# BpodFSM_r2_3.net
KiCad netlist of a schematic drawn in EAGLE
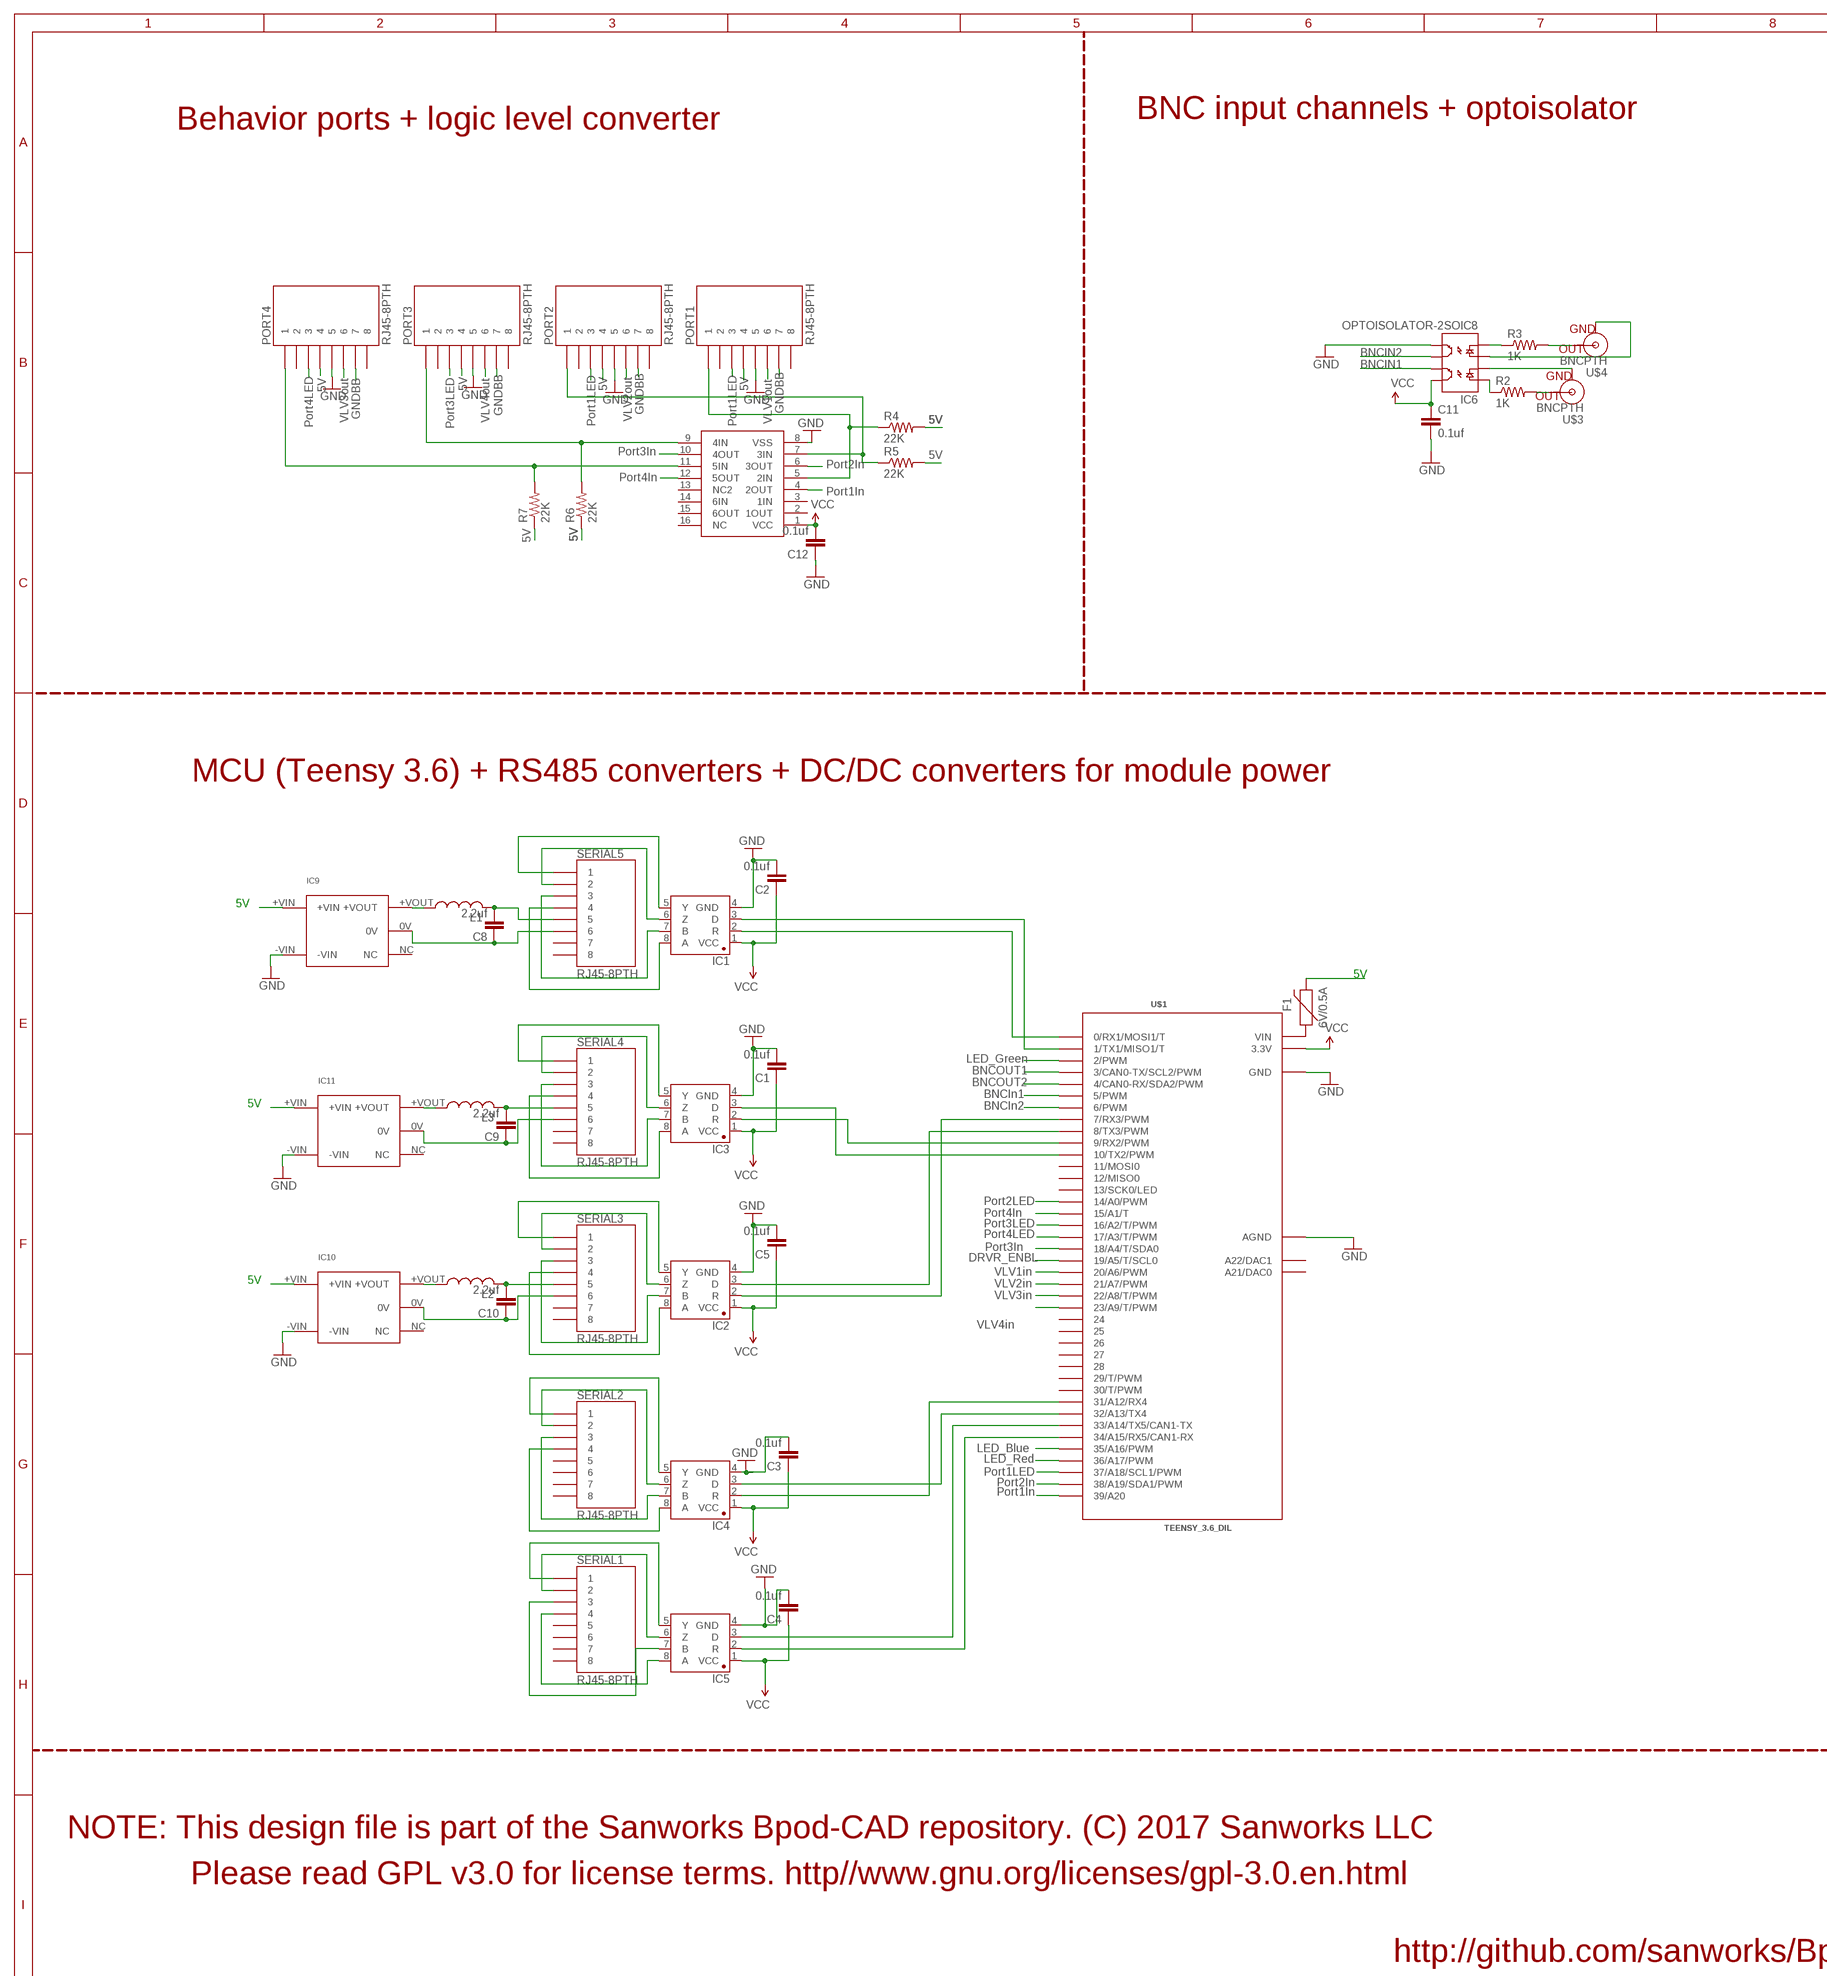
[diagram p0: schematic, sheet 1, part 1 of 2]
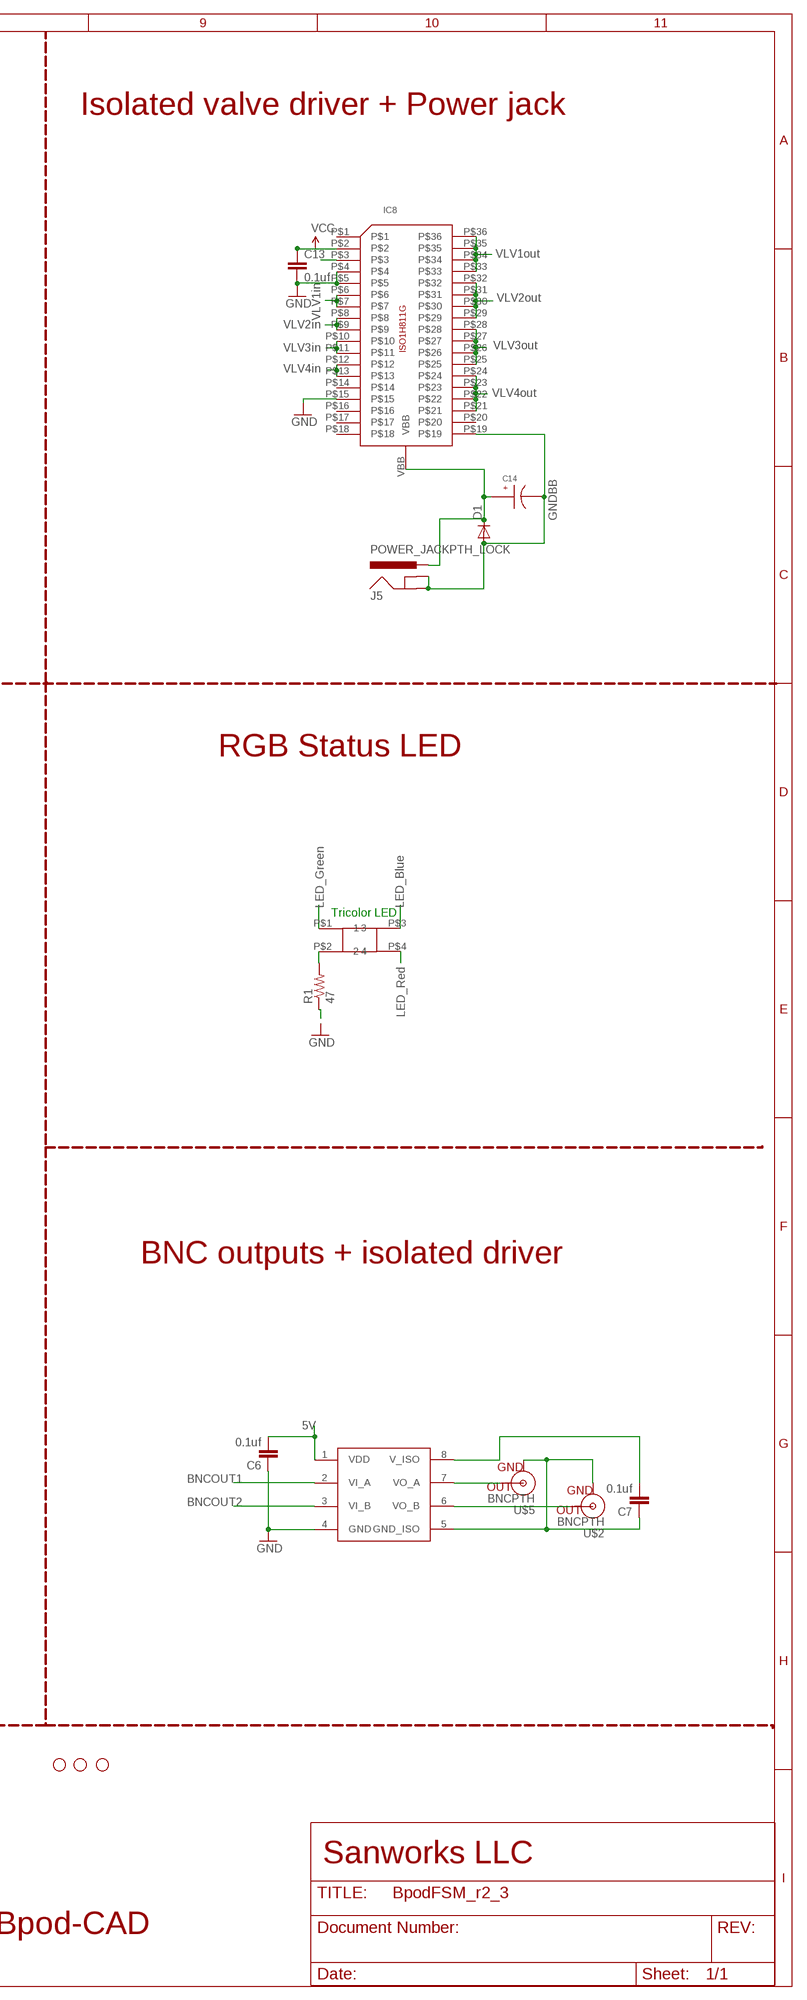
[diagram p1: schematic, sheet 1, part 2 of 2]

(export (version "E")
  (design (tool "Eeschema 10.0.6"))
  (components
    (comp (ref "C1")
      (value "0.1uf")
      (footprint "eagle-import:1206")
      (libsource (lib "eagle-import") (part "CAP1206"))
    )
    (comp (ref "C2")
      (value "0.1uf")
      (footprint "eagle-import:1206")
      (libsource (lib "eagle-import") (part "CAP1206"))
    )
    (comp (ref "C3")
      (value "0.1uf")
      (footprint "eagle-import:1206")
      (libsource (lib "eagle-import") (part "CAP1206"))
    )
    (comp (ref "C4")
      (value "0.1uf")
      (footprint "eagle-import:1206")
      (libsource (lib "eagle-import") (part "CAP1206"))
    )
    (comp (ref "C5")
      (value "0.1uf")
      (footprint "eagle-import:1206")
      (libsource (lib "eagle-import") (part "CAP1206"))
    )
    (comp (ref "C6")
      (value "0.1uf")
      (footprint "eagle-import:1206")
      (libsource (lib "eagle-import") (part "CAP1206"))
    )
    (comp (ref "C7")
      (value "0.1uf")
      (footprint "eagle-import:1206")
      (libsource (lib "eagle-import") (part "CAP1206"))
    )
    (comp (ref "C8")
      (value "2.2uf")
      (footprint "eagle-import:1206")
      (libsource (lib "eagle-import") (part "CAP1206"))
    )
    (comp (ref "C9")
      (value "2.2uf")
      (footprint "eagle-import:1206")
      (libsource (lib "eagle-import") (part "CAP1206"))
    )
    (comp (ref "C10")
      (value "2.2uf")
      (footprint "eagle-import:1206")
      (libsource (lib "eagle-import") (part "CAP1206"))
    )
    (comp (ref "C11")
      (value "0.1uf")
      (footprint "eagle-import:1206")
      (libsource (lib "eagle-import") (part "CAP1206"))
    )
    (comp (ref "C12")
      (value "0.1uf")
      (footprint "eagle-import:1206")
      (libsource (lib "eagle-import") (part "CAP1206"))
    )
    (comp (ref "C13")
      (value "0.1uf")
      (footprint "eagle-import:1206")
      (libsource (lib "eagle-import") (part "CAP1206"))
    )
    (comp (ref "C14")
      (value "EEE-FK1H100UR")
      (footprint "eagle-import:EEE-FK1H100UR")
      (libsource (lib "eagle-import") (part "EEE-FK1H100UR"))
    )
    (comp (ref "D1")
      (value "DIODE-DO214AA")
      (footprint "eagle-import:DO214AA")
      (libsource (lib "eagle-import") (part "DIODE-DO214AA"))
    )
    (comp (ref "F1")
      (value "6V/0.5A")
      (footprint "eagle-import:1206")
      (libsource (lib "eagle-import") (part "PPTC_HALF-AMP"))
    )
    (comp (ref "IC1")
      (value "SN65HVD31DR")
      (footprint "eagle-import:SO08")
      (libsource (lib "eagle-import") (part "SN65HVD31DR"))
    )
    (comp (ref "IC2")
      (value "SN65HVD31DR")
      (footprint "eagle-import:SO08")
      (libsource (lib "eagle-import") (part "SN65HVD31DR"))
    )
    (comp (ref "IC3")
      (value "SN65HVD31DR")
      (footprint "eagle-import:SO08")
      (libsource (lib "eagle-import") (part "SN65HVD31DR"))
    )
    (comp (ref "IC4")
      (value "SN65HVD31DR")
      (footprint "eagle-import:SO08")
      (libsource (lib "eagle-import") (part "SN65HVD31DR"))
    )
    (comp (ref "IC5")
      (value "SN65HVD31DR")
      (footprint "eagle-import:SO08")
      (libsource (lib "eagle-import") (part "SN65HVD31DR"))
    )
    (comp (ref "IC6")
      (value "OPTOISOLATOR-2SOIC8")
      (footprint "eagle-import:SO08-2")
      (libsource (lib "eagle-import") (part "OPTOISOLATOR-2SOIC8"))
    )
    (comp (ref "IC7")
      (value "ADUM5240")
      (footprint "eagle-import:SO08")
      (libsource (lib "eagle-import") (part "ADUM5240"))
    )
    (comp (ref "IC8")
      (value "ISO1H811G")
      (footprint "eagle-import:ISO1H811G")
      (libsource (lib "eagle-import") (part "ISO1H811G"))
    )
    (comp (ref "IC9")
      (value "MTU1D0505MC")
      (footprint "eagle-import:MTU1D0505MC")
      (libsource (lib "eagle-import") (part "MTU1D0505MC"))
    )
    (comp (ref "IC10")
      (value "MTU1D0505MC")
      (footprint "eagle-import:MTU1D0505MC")
      (libsource (lib "eagle-import") (part "MTU1D0505MC"))
    )
    (comp (ref "IC11")
      (value "MTU1D0505MC")
      (footprint "eagle-import:MTU1D0505MC")
      (libsource (lib "eagle-import") (part "MTU1D0505MC"))
    )
    (comp (ref "IC12")
      (value "CD4050")
      (footprint "eagle-import:SO16")
      (libsource (lib "eagle-import") (part "CD4050"))
    )
    (comp (ref "J5")
      (value "POWER_JACKPTH_LOCK")
      (footprint "eagle-import:POWER_JACK_PTH_LOCK")
      (libsource (lib "eagle-import") (part "POWER_JACKPTH_LOCK"))
    )
    (comp (ref "JP3")
      (value "STAND-OFF")
      (footprint "eagle-import:STAND-OFF")
      (libsource (lib "eagle-import") (part "STAND-OFF"))
    )
    (comp (ref "JP4")
      (value "STAND-OFF")
      (footprint "eagle-import:STAND-OFF")
      (libsource (lib "eagle-import") (part "STAND-OFF"))
    )
    (comp (ref "JP5")
      (value "STAND-OFF")
      (footprint "eagle-import:STAND-OFF")
      (libsource (lib "eagle-import") (part "STAND-OFF"))
    )
    (comp (ref "L1")
      (value "L-USL3225M")
      (footprint "eagle-import:L3225M")
      (libsource (lib "eagle-import") (part "L-USL3225M"))
    )
    (comp (ref "L2")
      (value "L-USL3225M")
      (footprint "eagle-import:L3225M")
      (libsource (lib "eagle-import") (part "L-USL3225M"))
    )
    (comp (ref "L3")
      (value "L-USL3225M")
      (footprint "eagle-import:L3225M")
      (libsource (lib "eagle-import") (part "L-USL3225M"))
    )
    (comp (ref "PORT1")
      (value "RJ45-8PTH")
      (footprint "eagle-import:RJ45-8")
      (libsource (lib "eagle-import") (part "RJ45-8PTH"))
    )
    (comp (ref "PORT2")
      (value "RJ45-8PTH")
      (footprint "eagle-import:RJ45-8")
      (libsource (lib "eagle-import") (part "RJ45-8PTH"))
    )
    (comp (ref "PORT3")
      (value "RJ45-8PTH")
      (footprint "eagle-import:RJ45-8")
      (libsource (lib "eagle-import") (part "RJ45-8PTH"))
    )
    (comp (ref "PORT4")
      (value "RJ45-8PTH")
      (footprint "eagle-import:RJ45-8")
      (libsource (lib "eagle-import") (part "RJ45-8PTH"))
    )
    (comp (ref "R1")
      (value "47")
      (footprint "eagle-import:1206")
      (libsource (lib "eagle-import") (part "RESISTOR1206"))
    )
    (comp (ref "R2")
      (value "1K")
      (footprint "eagle-import:1206")
      (libsource (lib "eagle-import") (part "SparkFun-Resistors_RESISTOR1206"))
    )
    (comp (ref "R3")
      (value "1K")
      (footprint "eagle-import:1206")
      (libsource (lib "eagle-import") (part "SparkFun-Resistors_RESISTOR1206"))
    )
    (comp (ref "R4")
      (value "22K")
      (footprint "eagle-import:1206")
      (libsource (lib "eagle-import") (part "SparkFun-Resistors_RESISTOR1206"))
    )
    (comp (ref "R5")
      (value "22K")
      (footprint "eagle-import:1206")
      (libsource (lib "eagle-import") (part "SparkFun-Resistors_RESISTOR1206"))
    )
    (comp (ref "R6")
      (value "22K")
      (footprint "eagle-import:1206")
      (libsource (lib "eagle-import") (part "SparkFun-Resistors_RESISTOR1206"))
    )
    (comp (ref "R7")
      (value "22K")
      (footprint "eagle-import:1206")
      (libsource (lib "eagle-import") (part "SparkFun-Resistors_RESISTOR1206"))
    )
    (comp (ref "SERIAL1")
      (value "RJ45-8PTH")
      (footprint "eagle-import:RJ45-8")
      (libsource (lib "eagle-import") (part "RJ45-8PTH"))
    )
    (comp (ref "SERIAL2")
      (value "RJ45-8PTH")
      (footprint "eagle-import:RJ45-8")
      (libsource (lib "eagle-import") (part "RJ45-8PTH"))
    )
    (comp (ref "SERIAL3")
      (value "RJ45-8PTH")
      (footprint "eagle-import:RJ45-8")
      (libsource (lib "eagle-import") (part "RJ45-8PTH"))
    )
    (comp (ref "SERIAL4")
      (value "RJ45-8PTH")
      (footprint "eagle-import:RJ45-8")
      (libsource (lib "eagle-import") (part "RJ45-8PTH"))
    )
    (comp (ref "SERIAL5")
      (value "RJ45-8PTH")
      (footprint "eagle-import:RJ45-8")
      (libsource (lib "eagle-import") (part "RJ45-8PTH"))
    )
    (comp (ref "U$1")
      (value "TEENSY_3.6_DIL")
      (footprint "eagle-import:TEENSY_3.6_DIL")
      (libsource (lib "eagle-import") (part "TEENSY_3.6_DIL"))
    )
    (comp (ref "U$2")
      (value "BNCPTH")
      (footprint "eagle-import:BNC")
      (libsource (lib "eagle-import") (part "BNCPTH"))
    )
    (comp (ref "U$3")
      (value "BNCPTH")
      (footprint "eagle-import:BNC")
      (libsource (lib "eagle-import") (part "BNCPTH"))
    )
    (comp (ref "U$4")
      (value "BNCPTH")
      (footprint "eagle-import:BNC")
      (libsource (lib "eagle-import") (part "BNCPTH"))
    )
    (comp (ref "U$5")
      (value "BNCPTH")
      (footprint "eagle-import:BNC")
      (libsource (lib "eagle-import") (part "BNCPTH"))
    )
    (comp (ref "U$8")
      (value "SQUARE_TRICOLOR_LED")
      (footprint "eagle-import:SQUARE_TRICOLOR_LED")
      (libsource (lib "eagle-import") (part "SQUARE_TRICOLOR_LED"))
    )
  )
  (nets
    (net (code "1") (name "/5V") (class "Default")
      (node (ref "C6") (pin "2") (pinfunction "2_2") (pintype "passive"))
      (node (ref "F1") (pin "2") (pinfunction "2_2") (pintype "bidirectional"))
      (node (ref "IC10") (pin "+VIN") (pinfunction "+VIN_+VIN") (pintype "bidirectional"))
      (node (ref "IC11") (pin "+VIN") (pinfunction "+VIN_+VIN") (pintype "bidirectional"))
      (node (ref "IC7") (pin "1") (pinfunction "VDD_1") (pintype "bidirectional"))
      (node (ref "IC9") (pin "+VIN") (pinfunction "+VIN_+VIN") (pintype "bidirectional"))
      (node (ref "PORT1") (pin "4") (pinfunction "4_4") (pintype "bidirectional"))
      (node (ref "PORT2") (pin "4") (pinfunction "4_4") (pintype "bidirectional"))
      (node (ref "PORT3") (pin "4") (pinfunction "4_4") (pintype "bidirectional"))
      (node (ref "PORT4") (pin "4") (pinfunction "4_4") (pintype "bidirectional"))
      (node (ref "R4") (pin "2") (pinfunction "2_2") (pintype "passive"))
      (node (ref "R5") (pin "2") (pinfunction "2_2") (pintype "passive"))
      (node (ref "R6") (pin "1") (pinfunction "1_1") (pintype "passive"))
      (node (ref "R7") (pin "1") (pinfunction "1_1") (pintype "passive"))
    )
    (net (code "2") (name "/BNCIN1") (class "Default")
      (node (ref "IC6") (pin "7") (pinfunction "EM1_7") (pintype "bidirectional"))
      (node (ref "U$1") (pin "6") (pinfunction "6/PWM_6") (pintype "bidirectional"))
    )
    (net (code "3") (name "/BNCIN2") (class "Default")
      (node (ref "IC6") (pin "6") (pinfunction "CL2_6") (pintype "bidirectional"))
      (node (ref "U$1") (pin "5") (pinfunction "5/PWM_5") (pintype "bidirectional"))
    )
    (net (code "4") (name "/BNCOUT1") (class "Default")
      (node (ref "IC7") (pin "3") (pinfunction "VI_B_3") (pintype "bidirectional"))
      (node (ref "U$1") (pin "4") (pinfunction "4/CAN0-RX/SDA2/PWM_4") (pintype "bidirectional"))
    )
    (net (code "5") (name "/BNCOUT2") (class "Default")
      (node (ref "IC7") (pin "2") (pinfunction "VI_A_2") (pintype "bidirectional"))
      (node (ref "U$1") (pin "3") (pinfunction "3/CAN0-TX/SCL2/PWM_3") (pintype "bidirectional"))
    )
    (net (code "6") (name "/DRVR_ENBL") (class "Default")
      (node (ref "IC8") (pin "P$3") (pinfunction "P$3_P$3") (pintype "bidirectional"))
      (node (ref "U$1") (pin "19/A5") (pinfunction "19/A5/T/SCL0_19/A5") (pintype "bidirectional"))
    )
    (net (code "7") (name "/GNDBB") (class "Default")
      (node (ref "C14") (pin "CATHODE") (pinfunction "CATHODE_CATHODE") (pintype "bidirectional"))
      (node (ref "D1") (pin "A") (pinfunction "A_A") (pintype "passive"))
      (node (ref "IC8") (pin "P$19") (pinfunction "P$19_P$19") (pintype "bidirectional"))
      (node (ref "J5") (pin "GND") (pinfunction "GND_GND") (pintype "bidirectional"))
      (node (ref "J5") (pin "GNDBREAK") (pinfunction "GNDBREAK_GNDBREAK") (pintype "bidirectional"))
      (node (ref "PORT1") (pin "7") (pinfunction "7_7") (pintype "bidirectional"))
      (node (ref "PORT2") (pin "7") (pinfunction "7_7") (pintype "bidirectional"))
      (node (ref "PORT3") (pin "7") (pinfunction "7_7") (pintype "bidirectional"))
      (node (ref "PORT4") (pin "7") (pinfunction "7_7") (pintype "bidirectional"))
    )
    (net (code "8") (name "/LED_BLUE") (class "Default")
      (node (ref "U$1") (pin "35/A16") (pinfunction "35/A16/PWM_35/A16") (pintype "bidirectional"))
      (node (ref "U$8") (pin "P$3") (pinfunction "3_P$3") (pintype "bidirectional"))
    )
    (net (code "9") (name "/LED_GREEN") (class "Default")
      (node (ref "U$1") (pin "2") (pinfunction "2/PWM_2") (pintype "bidirectional"))
      (node (ref "U$8") (pin "P$1") (pinfunction "1_P$1") (pintype "bidirectional"))
    )
    (net (code "10") (name "/LED_RED") (class "Default")
      (node (ref "U$1") (pin "36/A17") (pinfunction "36/A17/PWM_36/A17") (pintype "bidirectional"))
      (node (ref "U$8") (pin "P$4") (pinfunction "4_P$4") (pintype "bidirectional"))
    )
    (net (code "11") (name "/PORT1IN") (class "Default")
      (node (ref "IC12") (pin "4") (pinfunction "2OUT_4") (pintype "bidirectional"))
      (node (ref "U$1") (pin "39/A20") (pinfunction "39/A20_39/A20") (pintype "bidirectional"))
    )
    (net (code "12") (name "/PORT1LED") (class "Default")
      (node (ref "PORT1") (pin "3") (pinfunction "3_3") (pintype "bidirectional"))
      (node (ref "U$1") (pin "37/A18") (pinfunction "37/A18/SCL1/PWM_37/A18") (pintype "bidirectional"))
    )
    (net (code "13") (name "/PORT2IN") (class "Default")
      (node (ref "IC12") (pin "6") (pinfunction "3OUT_6") (pintype "bidirectional"))
      (node (ref "U$1") (pin "38/A19") (pinfunction "38/A19/SDA1/PWM_38/A19") (pintype "bidirectional"))
    )
    (net (code "14") (name "/PORT2LED") (class "Default")
      (node (ref "PORT2") (pin "3") (pinfunction "3_3") (pintype "bidirectional"))
      (node (ref "U$1") (pin "14/A0") (pinfunction "14/A0/PWM_14/A0") (pintype "bidirectional"))
    )
    (net (code "15") (name "/PORT3IN") (class "Default")
      (node (ref "IC12") (pin "10") (pinfunction "4OUT_10") (pintype "bidirectional"))
      (node (ref "U$1") (pin "18/A4") (pinfunction "18/A4/T/SDA0_18/A4") (pintype "bidirectional"))
    )
    (net (code "16") (name "/PORT3LED") (class "Default")
      (node (ref "PORT3") (pin "3") (pinfunction "3_3") (pintype "bidirectional"))
      (node (ref "U$1") (pin "16/A2") (pinfunction "16/A2/T/PWM_16/A2") (pintype "bidirectional"))
    )
    (net (code "17") (name "/PORT4IN") (class "Default")
      (node (ref "IC12") (pin "12") (pinfunction "5OUT_12") (pintype "bidirectional"))
      (node (ref "U$1") (pin "15/A1") (pinfunction "15/A1/T_15/A1") (pintype "bidirectional"))
    )
    (net (code "18") (name "/PORT4LED") (class "Default")
      (node (ref "PORT4") (pin "3") (pinfunction "3_3") (pintype "bidirectional"))
      (node (ref "U$1") (pin "17/A3") (pinfunction "17/A3/T/PWM_17/A3") (pintype "bidirectional"))
    )
    (net (code "19") (name "/VLV1IN") (class "Default")
      (node (ref "IC8") (pin "P$6") (pinfunction "P$6_P$6") (pintype "bidirectional"))
      (node (ref "IC8") (pin "P$7") (pinfunction "P$7_P$7") (pintype "bidirectional"))
      (node (ref "U$1") (pin "23/A9") (pinfunction "23/A9/T/PWM_23/A9") (pintype "bidirectional"))
    )
    (net (code "20") (name "/VLV1OUT") (class "Default")
      (node (ref "IC8") (pin "P$33") (pinfunction "P$33_P$33") (pintype "bidirectional"))
      (node (ref "IC8") (pin "P$34") (pinfunction "P$34_P$34") (pintype "bidirectional"))
      (node (ref "IC8") (pin "P$35") (pinfunction "P$35_P$35") (pintype "bidirectional"))
      (node (ref "IC8") (pin "P$36") (pinfunction "P$36_P$36") (pintype "bidirectional"))
      (node (ref "PORT1") (pin "6") (pinfunction "6_6") (pintype "bidirectional"))
    )
    (net (code "21") (name "/VLV2IN") (class "Default")
      (node (ref "IC8") (pin "P$8") (pinfunction "P$8_P$8") (pintype "bidirectional"))
      (node (ref "IC8") (pin "P$9") (pinfunction "P$9_P$9") (pintype "bidirectional"))
      (node (ref "U$1") (pin "22/A8") (pinfunction "22/A8/T/PWM_22/A8") (pintype "bidirectional"))
    )
    (net (code "22") (name "/VLV2OUT") (class "Default")
      (node (ref "IC8") (pin "P$29") (pinfunction "P$29_P$29") (pintype "bidirectional"))
      (node (ref "IC8") (pin "P$30") (pinfunction "P$30_P$30") (pintype "bidirectional"))
      (node (ref "IC8") (pin "P$31") (pinfunction "P$31_P$31") (pintype "bidirectional"))
      (node (ref "IC8") (pin "P$32") (pinfunction "P$32_P$32") (pintype "bidirectional"))
      (node (ref "PORT2") (pin "6") (pinfunction "6_6") (pintype "bidirectional"))
    )
    (net (code "23") (name "/VLV3IN") (class "Default")
      (node (ref "IC8") (pin "P$12") (pinfunction "P$12_P$12") (pintype "bidirectional"))
      (node (ref "IC8") (pin "P$13") (pinfunction "P$13_P$13") (pintype "bidirectional"))
      (node (ref "U$1") (pin "20/A6") (pinfunction "20/A6/PWM_20/A6") (pintype "bidirectional"))
    )
    (net (code "24") (name "/VLV3OUT") (class "Default")
      (node (ref "IC8") (pin "P$21") (pinfunction "P$21_P$21") (pintype "bidirectional"))
      (node (ref "IC8") (pin "P$22") (pinfunction "P$22_P$22") (pintype "bidirectional"))
      (node (ref "IC8") (pin "P$23") (pinfunction "P$23_P$23") (pintype "bidirectional"))
      (node (ref "IC8") (pin "P$24") (pinfunction "P$24_P$24") (pintype "bidirectional"))
      (node (ref "PORT3") (pin "6") (pinfunction "6_6") (pintype "bidirectional"))
    )
    (net (code "25") (name "/VLV4IN") (class "Default")
      (node (ref "IC8") (pin "P$10") (pinfunction "P$10_P$10") (pintype "bidirectional"))
      (node (ref "IC8") (pin "P$11") (pinfunction "P$11_P$11") (pintype "bidirectional"))
      (node (ref "U$1") (pin "21/A7") (pinfunction "21/A7/PWM_21/A7") (pintype "bidirectional"))
    )
    (net (code "26") (name "/VLV4OUT") (class "Default")
      (node (ref "IC8") (pin "P$25") (pinfunction "P$25_P$25") (pintype "bidirectional"))
      (node (ref "IC8") (pin "P$26") (pinfunction "P$26_P$26") (pintype "bidirectional"))
      (node (ref "IC8") (pin "P$27") (pinfunction "P$27_P$27") (pintype "bidirectional"))
      (node (ref "IC8") (pin "P$28") (pinfunction "P$28_P$28") (pintype "bidirectional"))
      (node (ref "PORT4") (pin "6") (pinfunction "6_6") (pintype "bidirectional"))
    )
    (net (code "27") (name "GND") (class "Default")
      (node (ref "C1") (pin "2") (pinfunction "2_2") (pintype "passive"))
      (node (ref "C11") (pin "2") (pinfunction "2_2") (pintype "passive"))
      (node (ref "C12") (pin "1") (pinfunction "1_1") (pintype "passive"))
      (node (ref "C13") (pin "2") (pinfunction "2_2") (pintype "passive"))
      (node (ref "C2") (pin "2") (pinfunction "2_2") (pintype "passive"))
      (node (ref "C3") (pin "2") (pinfunction "2_2") (pintype "passive"))
      (node (ref "C4") (pin "2") (pinfunction "2_2") (pintype "passive"))
      (node (ref "C5") (pin "2") (pinfunction "2_2") (pintype "passive"))
      (node (ref "C6") (pin "1") (pinfunction "1_1") (pintype "passive"))
      (node (ref "IC1") (pin "4") (pinfunction "GND_4") (pintype "bidirectional"))
      (node (ref "IC10") (pin "-VIN") (pinfunction "-VIN_-VIN") (pintype "bidirectional"))
      (node (ref "IC11") (pin "-VIN") (pinfunction "-VIN_-VIN") (pintype "bidirectional"))
      (node (ref "IC12") (pin "8") (pinfunction "VSS_8") (pintype "bidirectional"))
      (node (ref "IC2") (pin "4") (pinfunction "GND_4") (pintype "bidirectional"))
      (node (ref "IC3") (pin "4") (pinfunction "GND_4") (pintype "bidirectional"))
      (node (ref "IC4") (pin "4") (pinfunction "GND_4") (pintype "bidirectional"))
      (node (ref "IC5") (pin "4") (pinfunction "GND_4") (pintype "bidirectional"))
      (node (ref "IC6") (pin "5") (pinfunction "EM2_5") (pintype "bidirectional"))
      (node (ref "IC7") (pin "4") (pinfunction "GND_4") (pintype "bidirectional"))
      (node (ref "IC8") (pin "P$15") (pinfunction "P$15_P$15") (pintype "bidirectional"))
      (node (ref "IC8") (pin "P$4") (pinfunction "P$4_P$4") (pintype "bidirectional"))
      (node (ref "IC8") (pin "P$5") (pinfunction "P$5_P$5") (pintype "bidirectional"))
      (node (ref "IC9") (pin "-VIN") (pinfunction "-VIN_-VIN") (pintype "bidirectional"))
      (node (ref "PORT1") (pin "5") (pinfunction "5_5") (pintype "bidirectional"))
      (node (ref "PORT2") (pin "5") (pinfunction "5_5") (pintype "bidirectional"))
      (node (ref "PORT3") (pin "5") (pinfunction "5_5") (pintype "bidirectional"))
      (node (ref "PORT4") (pin "5") (pinfunction "5_5") (pintype "bidirectional"))
      (node (ref "R1") (pin "1") (pinfunction "1_1") (pintype "passive"))
      (node (ref "U$1") (pin "AGND") (pinfunction "AGND_AGND") (pintype "power_in"))
      (node (ref "U$1") (pin "GND") (pinfunction "GND_GND") (pintype "power_in"))
      (node (ref "U$1") (pin "GND1") (pinfunction "GND_GND1") (pintype "power_in"))
    )
    (net (code "28") (name "Net-(C8-Pad1)") (class "Default")
      (node (ref "C8") (pin "1") (pinfunction "1_1") (pintype "passive"))
      (node (ref "IC9") (pin "0V") (pinfunction "0V_0V") (pintype "bidirectional"))
      (node (ref "SERIAL5") (pin "6") (pinfunction "6_6") (pintype "bidirectional"))
    )
    (net (code "29") (name "Net-(C8-Pad2)") (class "Default")
      (node (ref "C8") (pin "2") (pinfunction "2_2") (pintype "passive"))
      (node (ref "L1") (pin "2") (pinfunction "2_2") (pintype "passive"))
      (node (ref "SERIAL5") (pin "5") (pinfunction "5_5") (pintype "bidirectional"))
    )
    (net (code "30") (name "Net-(C9-Pad1)") (class "Default")
      (node (ref "C9") (pin "1") (pinfunction "1_1") (pintype "passive"))
      (node (ref "IC11") (pin "0V") (pinfunction "0V_0V") (pintype "bidirectional"))
      (node (ref "SERIAL4") (pin "6") (pinfunction "6_6") (pintype "bidirectional"))
    )
    (net (code "31") (name "Net-(C9-Pad2)") (class "Default")
      (node (ref "C9") (pin "2") (pinfunction "2_2") (pintype "passive"))
      (node (ref "L3") (pin "2") (pinfunction "2_2") (pintype "passive"))
      (node (ref "SERIAL4") (pin "5") (pinfunction "5_5") (pintype "bidirectional"))
    )
    (net (code "32") (name "Net-(C10-Pad1)") (class "Default")
      (node (ref "C10") (pin "1") (pinfunction "1_1") (pintype "passive"))
      (node (ref "IC10") (pin "0V") (pinfunction "0V_0V") (pintype "bidirectional"))
      (node (ref "SERIAL3") (pin "6") (pinfunction "6_6") (pintype "bidirectional"))
    )
    (net (code "33") (name "Net-(C10-Pad2)") (class "Default")
      (node (ref "C10") (pin "2") (pinfunction "2_2") (pintype "passive"))
      (node (ref "L2") (pin "2") (pinfunction "2_2") (pintype "passive"))
      (node (ref "SERIAL3") (pin "5") (pinfunction "5_5") (pintype "bidirectional"))
    )
    (net (code "34") (name "Net-(C14-PadANODE)") (class "Default")
      (node (ref "C14") (pin "ANODE") (pinfunction "ANODE_ANODE") (pintype "bidirectional"))
      (node (ref "D1") (pin "C") (pinfunction "C_C") (pintype "passive"))
      (node (ref "IC8") (pin "VBB") (pinfunction "VBB_VBB") (pintype "bidirectional"))
      (node (ref "J5") (pin "PWR") (pinfunction "PWR_PWR") (pintype "bidirectional"))
    )
    (net (code "35") (name "Net-(F1-Pad1)") (class "Default")
      (node (ref "F1") (pin "1") (pinfunction "1_1") (pintype "bidirectional"))
      (node (ref "U$1") (pin "VIN") (pinfunction "VIN_VIN") (pintype "power_in"))
    )
    (net (code "36") (name "Net-(IC1-A)") (class "Default")
      (node (ref "IC1") (pin "8") (pinfunction "A_8") (pintype "bidirectional"))
      (node (ref "SERIAL5") (pin "4") (pinfunction "4_4") (pintype "bidirectional"))
    )
    (net (code "37") (name "Net-(IC1-B)") (class "Default")
      (node (ref "IC1") (pin "7") (pinfunction "B_7") (pintype "bidirectional"))
      (node (ref "SERIAL5") (pin "3") (pinfunction "3_3") (pintype "bidirectional"))
    )
    (net (code "38") (name "Net-(IC1-D)") (class "Default")
      (node (ref "IC1") (pin "3") (pinfunction "D_3") (pintype "bidirectional"))
      (node (ref "U$1") (pin "1") (pinfunction "1/TX1/MISO1/T_1") (pintype "bidirectional"))
    )
    (net (code "39") (name "Net-(IC1-R)") (class "Default")
      (node (ref "IC1") (pin "2") (pinfunction "R_2") (pintype "bidirectional"))
      (node (ref "U$1") (pin "0") (pinfunction "0/RX1/MOSI1/T_0") (pintype "bidirectional"))
    )
    (net (code "40") (name "Net-(IC1-Y)") (class "Default")
      (node (ref "IC1") (pin "5") (pinfunction "Y_5") (pintype "bidirectional"))
      (node (ref "SERIAL5") (pin "1") (pinfunction "1_1") (pintype "bidirectional"))
    )
    (net (code "41") (name "Net-(IC1-Z)") (class "Default")
      (node (ref "IC1") (pin "6") (pinfunction "Z_6") (pintype "bidirectional"))
      (node (ref "SERIAL5") (pin "2") (pinfunction "2_2") (pintype "bidirectional"))
    )
    (net (code "42") (name "Net-(IC2-A)") (class "Default")
      (node (ref "IC2") (pin "8") (pinfunction "A_8") (pintype "bidirectional"))
      (node (ref "SERIAL3") (pin "4") (pinfunction "4_4") (pintype "bidirectional"))
    )
    (net (code "43") (name "Net-(IC2-B)") (class "Default")
      (node (ref "IC2") (pin "7") (pinfunction "B_7") (pintype "bidirectional"))
      (node (ref "SERIAL3") (pin "3") (pinfunction "3_3") (pintype "bidirectional"))
    )
    (net (code "44") (name "Net-(IC2-D)") (class "Default")
      (node (ref "IC2") (pin "3") (pinfunction "D_3") (pintype "bidirectional"))
      (node (ref "U$1") (pin "8") (pinfunction "8/TX3/PWM_8") (pintype "bidirectional"))
    )
    (net (code "45") (name "Net-(IC2-R)") (class "Default")
      (node (ref "IC2") (pin "2") (pinfunction "R_2") (pintype "bidirectional"))
      (node (ref "U$1") (pin "7") (pinfunction "7/RX3/PWM_7") (pintype "bidirectional"))
    )
    (net (code "46") (name "Net-(IC2-Y)") (class "Default")
      (node (ref "IC2") (pin "5") (pinfunction "Y_5") (pintype "bidirectional"))
      (node (ref "SERIAL3") (pin "1") (pinfunction "1_1") (pintype "bidirectional"))
    )
    (net (code "47") (name "Net-(IC2-Z)") (class "Default")
      (node (ref "IC2") (pin "6") (pinfunction "Z_6") (pintype "bidirectional"))
      (node (ref "SERIAL3") (pin "2") (pinfunction "2_2") (pintype "bidirectional"))
    )
    (net (code "48") (name "Net-(IC3-A)") (class "Default")
      (node (ref "IC3") (pin "8") (pinfunction "A_8") (pintype "bidirectional"))
      (node (ref "SERIAL4") (pin "4") (pinfunction "4_4") (pintype "bidirectional"))
    )
    (net (code "49") (name "Net-(IC3-B)") (class "Default")
      (node (ref "IC3") (pin "7") (pinfunction "B_7") (pintype "bidirectional"))
      (node (ref "SERIAL4") (pin "3") (pinfunction "3_3") (pintype "bidirectional"))
    )
    (net (code "50") (name "Net-(IC3-D)") (class "Default")
      (node (ref "IC3") (pin "3") (pinfunction "D_3") (pintype "bidirectional"))
      (node (ref "U$1") (pin "10") (pinfunction "10/TX2/PWM_10") (pintype "bidirectional"))
    )
    (net (code "51") (name "Net-(IC3-R)") (class "Default")
      (node (ref "IC3") (pin "2") (pinfunction "R_2") (pintype "bidirectional"))
      (node (ref "U$1") (pin "9") (pinfunction "9/RX2/PWM_9") (pintype "bidirectional"))
    )
    (net (code "52") (name "Net-(IC3-Y)") (class "Default")
      (node (ref "IC3") (pin "5") (pinfunction "Y_5") (pintype "bidirectional"))
      (node (ref "SERIAL4") (pin "1") (pinfunction "1_1") (pintype "bidirectional"))
    )
    (net (code "53") (name "Net-(IC3-Z)") (class "Default")
      (node (ref "IC3") (pin "6") (pinfunction "Z_6") (pintype "bidirectional"))
      (node (ref "SERIAL4") (pin "2") (pinfunction "2_2") (pintype "bidirectional"))
    )
    (net (code "54") (name "Net-(IC4-A)") (class "Default")
      (node (ref "IC4") (pin "8") (pinfunction "A_8") (pintype "bidirectional"))
      (node (ref "SERIAL2") (pin "4") (pinfunction "4_4") (pintype "bidirectional"))
    )
    (net (code "55") (name "Net-(IC4-B)") (class "Default")
      (node (ref "IC4") (pin "7") (pinfunction "B_7") (pintype "bidirectional"))
      (node (ref "SERIAL2") (pin "3") (pinfunction "3_3") (pintype "bidirectional"))
    )
    (net (code "56") (name "Net-(IC4-D)") (class "Default")
      (node (ref "IC4") (pin "3") (pinfunction "D_3") (pintype "bidirectional"))
      (node (ref "U$1") (pin "32/A13") (pinfunction "32/A13/TX4_32/A13") (pintype "bidirectional"))
    )
    (net (code "57") (name "Net-(IC4-R)") (class "Default")
      (node (ref "IC4") (pin "2") (pinfunction "R_2") (pintype "bidirectional"))
      (node (ref "U$1") (pin "31/A12") (pinfunction "31/A12/RX4_31/A12") (pintype "bidirectional"))
    )
    (net (code "58") (name "Net-(IC4-Y)") (class "Default")
      (node (ref "IC4") (pin "5") (pinfunction "Y_5") (pintype "bidirectional"))
      (node (ref "SERIAL2") (pin "1") (pinfunction "1_1") (pintype "bidirectional"))
    )
    (net (code "59") (name "Net-(IC4-Z)") (class "Default")
      (node (ref "IC4") (pin "6") (pinfunction "Z_6") (pintype "bidirectional"))
      (node (ref "SERIAL2") (pin "2") (pinfunction "2_2") (pintype "bidirectional"))
    )
    (net (code "60") (name "Net-(IC5-A)") (class "Default")
      (node (ref "IC5") (pin "8") (pinfunction "A_8") (pintype "bidirectional"))
      (node (ref "SERIAL1") (pin "4") (pinfunction "4_4") (pintype "bidirectional"))
    )
    (net (code "61") (name "Net-(IC5-B)") (class "Default")
      (node (ref "IC5") (pin "7") (pinfunction "B_7") (pintype "bidirectional"))
      (node (ref "SERIAL1") (pin "3") (pinfunction "3_3") (pintype "bidirectional"))
    )
    (net (code "62") (name "Net-(IC5-D)") (class "Default")
      (node (ref "IC5") (pin "3") (pinfunction "D_3") (pintype "bidirectional"))
      (node (ref "U$1") (pin "33/A14") (pinfunction "33/A14/TX5/CAN1-TX_33/A14") (pintype "bidirectional"))
    )
    (net (code "63") (name "Net-(IC5-R)") (class "Default")
      (node (ref "IC5") (pin "2") (pinfunction "R_2") (pintype "bidirectional"))
      (node (ref "U$1") (pin "34/A15") (pinfunction "34/A15/RX5/CAN1-RX_34/A15") (pintype "bidirectional"))
    )
    (net (code "64") (name "Net-(IC5-Y)") (class "Default")
      (node (ref "IC5") (pin "5") (pinfunction "Y_5") (pintype "bidirectional"))
      (node (ref "SERIAL1") (pin "1") (pinfunction "1_1") (pintype "bidirectional"))
    )
    (net (code "65") (name "Net-(IC5-Z)") (class "Default")
      (node (ref "IC5") (pin "6") (pinfunction "Z_6") (pintype "bidirectional"))
      (node (ref "SERIAL1") (pin "2") (pinfunction "2_2") (pintype "bidirectional"))
    )
    (net (code "66") (name "Net-(IC6-A1)") (class "Default")
      (node (ref "IC6") (pin "1") (pinfunction "A1_1") (pintype "bidirectional"))
      (node (ref "R2") (pin "1") (pinfunction "1_1") (pintype "passive"))
    )
    (net (code "67") (name "Net-(IC6-A2)") (class "Default")
      (node (ref "IC6") (pin "3") (pinfunction "A2_3") (pintype "bidirectional"))
      (node (ref "U$4") (pin "GND") (pinfunction "GND_GND") (pintype "bidirectional"))
    )
    (net (code "68") (name "Net-(IC6-C1)") (class "Default")
      (node (ref "IC6") (pin "2") (pinfunction "C1_2") (pintype "bidirectional"))
      (node (ref "U$3") (pin "GND") (pinfunction "GND_GND") (pintype "bidirectional"))
    )
    (net (code "69") (name "Net-(IC6-C2)") (class "Default")
      (node (ref "IC6") (pin "4") (pinfunction "C2_4") (pintype "bidirectional"))
      (node (ref "R3") (pin "1") (pinfunction "1_1") (pintype "passive"))
    )
    (net (code "70") (name "Net-(IC7-GND_ISO)") (class "Default")
      (node (ref "C7") (pin "1") (pinfunction "1_1") (pintype "passive"))
      (node (ref "IC7") (pin "5") (pinfunction "GND_ISO_5") (pintype "bidirectional"))
      (node (ref "U$2") (pin "GND") (pinfunction "GND_GND") (pintype "bidirectional"))
      (node (ref "U$5") (pin "GND") (pinfunction "GND_GND") (pintype "bidirectional"))
    )
    (net (code "71") (name "Net-(IC7-VO_A)") (class "Default")
      (node (ref "IC7") (pin "7") (pinfunction "VO_A_7") (pintype "bidirectional"))
      (node (ref "U$5") (pin "S") (pinfunction "OUT_S") (pintype "bidirectional"))
    )
    (net (code "72") (name "Net-(IC7-VO_B)") (class "Default")
      (node (ref "IC7") (pin "6") (pinfunction "VO_B_6") (pintype "bidirectional"))
      (node (ref "U$2") (pin "S") (pinfunction "OUT_S") (pintype "bidirectional"))
    )
    (net (code "73") (name "Net-(IC7-V_ISO)") (class "Default")
      (node (ref "C7") (pin "2") (pinfunction "2_2") (pintype "passive"))
      (node (ref "IC7") (pin "8") (pinfunction "V_ISO_8") (pintype "bidirectional"))
    )
    (net (code "74") (name "Net-(IC9-Pad+VOUT)") (class "Default")
      (node (ref "IC9") (pin "+VOUT") (pinfunction "+VOUT_+VOUT") (pintype "bidirectional"))
      (node (ref "L1") (pin "1") (pinfunction "1_1") (pintype "passive"))
    )
    (net (code "75") (name "Net-(IC10-Pad+VOUT)") (class "Default")
      (node (ref "IC10") (pin "+VOUT") (pinfunction "+VOUT_+VOUT") (pintype "bidirectional"))
      (node (ref "L2") (pin "1") (pinfunction "1_1") (pintype "passive"))
    )
    (net (code "76") (name "Net-(IC11-Pad+VOUT)") (class "Default")
      (node (ref "IC11") (pin "+VOUT") (pinfunction "+VOUT_+VOUT") (pintype "bidirectional"))
      (node (ref "L3") (pin "1") (pinfunction "1_1") (pintype "passive"))
    )
    (net (code "77") (name "Net-(IC12-2IN)") (class "Default")
      (node (ref "IC12") (pin "5") (pinfunction "2IN_5") (pintype "bidirectional"))
      (node (ref "PORT1") (pin "1") (pinfunction "1_1") (pintype "bidirectional"))
      (node (ref "R4") (pin "1") (pinfunction "1_1") (pintype "passive"))
    )
    (net (code "78") (name "Net-(IC12-3IN)") (class "Default")
      (node (ref "IC12") (pin "7") (pinfunction "3IN_7") (pintype "bidirectional"))
      (node (ref "PORT2") (pin "1") (pinfunction "1_1") (pintype "bidirectional"))
      (node (ref "R5") (pin "1") (pinfunction "1_1") (pintype "passive"))
    )
    (net (code "79") (name "Net-(IC12-4IN)") (class "Default")
      (node (ref "IC12") (pin "9") (pinfunction "4IN_9") (pintype "bidirectional"))
      (node (ref "PORT3") (pin "1") (pinfunction "1_1") (pintype "bidirectional"))
      (node (ref "R6") (pin "2") (pinfunction "2_2") (pintype "passive"))
    )
    (net (code "80") (name "Net-(IC12-5IN)") (class "Default")
      (node (ref "IC12") (pin "11") (pinfunction "5IN_11") (pintype "bidirectional"))
      (node (ref "PORT4") (pin "1") (pinfunction "1_1") (pintype "bidirectional"))
      (node (ref "R7") (pin "2") (pinfunction "2_2") (pintype "passive"))
    )
    (net (code "81") (name "Net-(U$3-OUT)") (class "Default")
      (node (ref "R2") (pin "2") (pinfunction "2_2") (pintype "passive"))
      (node (ref "U$3") (pin "S") (pinfunction "OUT_S") (pintype "bidirectional"))
    )
    (net (code "82") (name "Net-(U$4-OUT)") (class "Default")
      (node (ref "R3") (pin "2") (pinfunction "2_2") (pintype "passive"))
      (node (ref "U$4") (pin "S") (pinfunction "OUT_S") (pintype "bidirectional"))
    )
    (net (code "83") (name "Net-(U$8-2)") (class "Default")
      (node (ref "R1") (pin "2") (pinfunction "2_2") (pintype "passive"))
      (node (ref "U$8") (pin "P$2") (pinfunction "2_P$2") (pintype "bidirectional"))
    )
    (net (code "84") (name "VCC") (class "Default")
      (node (ref "C1") (pin "1") (pinfunction "1_1") (pintype "passive"))
      (node (ref "C11") (pin "1") (pinfunction "1_1") (pintype "passive"))
      (node (ref "C12") (pin "2") (pinfunction "2_2") (pintype "passive"))
      (node (ref "C13") (pin "1") (pinfunction "1_1") (pintype "passive"))
      (node (ref "C2") (pin "1") (pinfunction "1_1") (pintype "passive"))
      (node (ref "C3") (pin "1") (pinfunction "1_1") (pintype "passive"))
      (node (ref "C4") (pin "1") (pinfunction "1_1") (pintype "passive"))
      (node (ref "C5") (pin "1") (pinfunction "1_1") (pintype "passive"))
      (node (ref "IC1") (pin "1") (pinfunction "VCC_1") (pintype "bidirectional"))
      (node (ref "IC12") (pin "1") (pinfunction "VCC_1") (pintype "bidirectional"))
      (node (ref "IC2") (pin "1") (pinfunction "VCC_1") (pintype "bidirectional"))
      (node (ref "IC3") (pin "1") (pinfunction "VCC_1") (pintype "bidirectional"))
      (node (ref "IC4") (pin "1") (pinfunction "VCC_1") (pintype "bidirectional"))
      (node (ref "IC5") (pin "1") (pinfunction "VCC_1") (pintype "bidirectional"))
      (node (ref "IC6") (pin "8") (pinfunction "CL1_8") (pintype "bidirectional"))
      (node (ref "IC8") (pin "P$2") (pinfunction "P$2_P$2") (pintype "bidirectional"))
      (node (ref "U$1") (pin "3.3V") (pinfunction "3.3V_3.3V") (pintype "power_in"))
      (node (ref "U$1") (pin "3.3V3") (pinfunction "3.3V_3.3V3") (pintype "power_in"))
    )
    (net (code "85") (name "unconnected-(IC8-PadP$1)") (class "Default")
      (node (ref "IC8") (pin "P$1") (pinfunction "P$1_P$1") (pintype "bidirectional"))
    )
    (net (code "86") (name "unconnected-(IC8-PadP$14)") (class "Default")
      (node (ref "IC8") (pin "P$14") (pinfunction "P$14_P$14") (pintype "bidirectional"))
    )
    (net (code "87") (name "unconnected-(IC8-PadP$16)") (class "Default")
      (node (ref "IC8") (pin "P$16") (pinfunction "P$16_P$16") (pintype "bidirectional"))
    )
    (net (code "88") (name "unconnected-(IC8-PadP$17)") (class "Default")
      (node (ref "IC8") (pin "P$17") (pinfunction "P$17_P$17") (pintype "bidirectional"))
    )
    (net (code "89") (name "unconnected-(IC8-PadP$18)") (class "Default")
      (node (ref "IC8") (pin "P$18") (pinfunction "P$18_P$18") (pintype "bidirectional"))
    )
    (net (code "90") (name "unconnected-(IC8-PadP$20)") (class "Default")
      (node (ref "IC8") (pin "P$20") (pinfunction "P$20_P$20") (pintype "bidirectional"))
    )
    (net (code "91") (name "unconnected-(IC9-PadNC)") (class "Default")
      (node (ref "IC9") (pin "NC") (pinfunction "NC_NC") (pintype "bidirectional"))
    )
    (net (code "92") (name "unconnected-(IC10-PadNC)") (class "Default")
      (node (ref "IC10") (pin "NC") (pinfunction "NC_NC") (pintype "bidirectional"))
    )
    (net (code "93") (name "unconnected-(IC11-PadNC)") (class "Default")
      (node (ref "IC11") (pin "NC") (pinfunction "NC_NC") (pintype "bidirectional"))
    )
    (net (code "94") (name "unconnected-(IC12-1IN-Pad3)") (class "Default")
      (node (ref "IC12") (pin "3") (pinfunction "1IN_3") (pintype "bidirectional"))
    )
    (net (code "95") (name "unconnected-(IC12-1OUT-Pad2)") (class "Default")
      (node (ref "IC12") (pin "2") (pinfunction "1OUT_2") (pintype "bidirectional"))
    )
    (net (code "96") (name "unconnected-(IC12-6IN-Pad14)") (class "Default")
      (node (ref "IC12") (pin "14") (pinfunction "6IN_14") (pintype "bidirectional"))
    )
    (net (code "97") (name "unconnected-(IC12-6OUT-Pad15)") (class "Default")
      (node (ref "IC12") (pin "15") (pinfunction "6OUT_15") (pintype "bidirectional"))
    )
    (net (code "98") (name "unconnected-(IC12-NC-Pad16)") (class "Default")
      (node (ref "IC12") (pin "16") (pinfunction "NC_16") (pintype "bidirectional"))
    )
    (net (code "99") (name "unconnected-(IC12-NC2-Pad13)") (class "Default")
      (node (ref "IC12") (pin "13") (pinfunction "NC2_13") (pintype "bidirectional"))
    )
    (net (code "100") (name "unconnected-(PORT1-Pad2)") (class "Default")
      (node (ref "PORT1") (pin "2") (pinfunction "2_2") (pintype "bidirectional"))
    )
    (net (code "101") (name "unconnected-(PORT1-Pad8)") (class "Default")
      (node (ref "PORT1") (pin "8") (pinfunction "8_8") (pintype "bidirectional"))
    )
    (net (code "102") (name "unconnected-(PORT2-Pad2)") (class "Default")
      (node (ref "PORT2") (pin "2") (pinfunction "2_2") (pintype "bidirectional"))
    )
    (net (code "103") (name "unconnected-(PORT2-Pad8)") (class "Default")
      (node (ref "PORT2") (pin "8") (pinfunction "8_8") (pintype "bidirectional"))
    )
    (net (code "104") (name "unconnected-(PORT3-Pad2)") (class "Default")
      (node (ref "PORT3") (pin "2") (pinfunction "2_2") (pintype "bidirectional"))
    )
    (net (code "105") (name "unconnected-(PORT3-Pad8)") (class "Default")
      (node (ref "PORT3") (pin "8") (pinfunction "8_8") (pintype "bidirectional"))
    )
    (net (code "106") (name "unconnected-(PORT4-Pad2)") (class "Default")
      (node (ref "PORT4") (pin "2") (pinfunction "2_2") (pintype "bidirectional"))
    )
    (net (code "107") (name "unconnected-(PORT4-Pad8)") (class "Default")
      (node (ref "PORT4") (pin "8") (pinfunction "8_8") (pintype "bidirectional"))
    )
    (net (code "108") (name "unconnected-(SERIAL1-Pad5)") (class "Default")
      (node (ref "SERIAL1") (pin "5") (pinfunction "5_5") (pintype "bidirectional"))
    )
    (net (code "109") (name "unconnected-(SERIAL1-Pad6)") (class "Default")
      (node (ref "SERIAL1") (pin "6") (pinfunction "6_6") (pintype "bidirectional"))
    )
    (net (code "110") (name "unconnected-(SERIAL1-Pad7)") (class "Default")
      (node (ref "SERIAL1") (pin "7") (pinfunction "7_7") (pintype "bidirectional"))
    )
    (net (code "111") (name "unconnected-(SERIAL1-Pad8)") (class "Default")
      (node (ref "SERIAL1") (pin "8") (pinfunction "8_8") (pintype "bidirectional"))
    )
    (net (code "112") (name "unconnected-(SERIAL2-Pad5)") (class "Default")
      (node (ref "SERIAL2") (pin "5") (pinfunction "5_5") (pintype "bidirectional"))
    )
    (net (code "113") (name "unconnected-(SERIAL2-Pad6)") (class "Default")
      (node (ref "SERIAL2") (pin "6") (pinfunction "6_6") (pintype "bidirectional"))
    )
    (net (code "114") (name "unconnected-(SERIAL2-Pad7)") (class "Default")
      (node (ref "SERIAL2") (pin "7") (pinfunction "7_7") (pintype "bidirectional"))
    )
    (net (code "115") (name "unconnected-(SERIAL2-Pad8)") (class "Default")
      (node (ref "SERIAL2") (pin "8") (pinfunction "8_8") (pintype "bidirectional"))
    )
    (net (code "116") (name "unconnected-(SERIAL3-Pad7)") (class "Default")
      (node (ref "SERIAL3") (pin "7") (pinfunction "7_7") (pintype "bidirectional"))
    )
    (net (code "117") (name "unconnected-(SERIAL3-Pad8)") (class "Default")
      (node (ref "SERIAL3") (pin "8") (pinfunction "8_8") (pintype "bidirectional"))
    )
    (net (code "118") (name "unconnected-(SERIAL4-Pad7)") (class "Default")
      (node (ref "SERIAL4") (pin "7") (pinfunction "7_7") (pintype "bidirectional"))
    )
    (net (code "119") (name "unconnected-(SERIAL4-Pad8)") (class "Default")
      (node (ref "SERIAL4") (pin "8") (pinfunction "8_8") (pintype "bidirectional"))
    )
    (net (code "120") (name "unconnected-(SERIAL5-Pad7)") (class "Default")
      (node (ref "SERIAL5") (pin "7") (pinfunction "7_7") (pintype "bidirectional"))
    )
    (net (code "121") (name "unconnected-(SERIAL5-Pad8)") (class "Default")
      (node (ref "SERIAL5") (pin "8") (pinfunction "8_8") (pintype "bidirectional"))
    )
    (net (code "122") (name "unconnected-(U$1-11{slash}MOSI0-Pad11)") (class "Default")
      (node (ref "U$1") (pin "11") (pinfunction "11/MOSI0_11") (pintype "bidirectional"))
    )
    (net (code "123") (name "unconnected-(U$1-12{slash}MISO0-Pad12)") (class "Default")
      (node (ref "U$1") (pin "12") (pinfunction "12/MISO0_12") (pintype "bidirectional"))
    )
    (net (code "124") (name "unconnected-(U$1-13{slash}SCK0{slash}LED-Pad13)") (class "Default")
      (node (ref "U$1") (pin "13") (pinfunction "13/SCK0/LED_13") (pintype "bidirectional"))
    )
    (net (code "125") (name "unconnected-(U$1-29{slash}T{slash}PWM-Pad29)") (class "Default")
      (node (ref "U$1") (pin "29") (pinfunction "29/T/PWM_29") (pintype "bidirectional"))
    )
    (net (code "126") (name "unconnected-(U$1-30{slash}T{slash}PWM-Pad30)") (class "Default")
      (node (ref "U$1") (pin "30") (pinfunction "30/T/PWM_30") (pintype "bidirectional"))
    )
    (net (code "127") (name "unconnected-(U$1-A21{slash}DAC0-PadA21)") (class "Default")
      (node (ref "U$1") (pin "A21") (pinfunction "A21/DAC0_A21") (pintype "bidirectional"))
    )
    (net (code "128") (name "unconnected-(U$1-A22{slash}DAC1-PadA22)") (class "Default")
      (node (ref "U$1") (pin "A22") (pinfunction "A22/DAC1_A22") (pintype "bidirectional"))
    )
    (net (code "129") (name "unconnected-(U$1-Pad24)") (class "Default")
      (node (ref "U$1") (pin "24") (pinfunction "24_24") (pintype "bidirectional"))
    )
    (net (code "130") (name "unconnected-(U$1-Pad25)") (class "Default")
      (node (ref "U$1") (pin "25") (pinfunction "25_25") (pintype "bidirectional"))
    )
    (net (code "131") (name "unconnected-(U$1-Pad26)") (class "Default")
      (node (ref "U$1") (pin "26") (pinfunction "26_26") (pintype "bidirectional"))
    )
    (net (code "132") (name "unconnected-(U$1-Pad27)") (class "Default")
      (node (ref "U$1") (pin "27") (pinfunction "27_27") (pintype "bidirectional"))
    )
    (net (code "133") (name "unconnected-(U$1-Pad28)") (class "Default")
      (node (ref "U$1") (pin "28") (pinfunction "28_28") (pintype "bidirectional"))
    )
  )
)
